# phase_leg_single_2L.net
KiCad netlist of a schematic drawn in Altium Designer
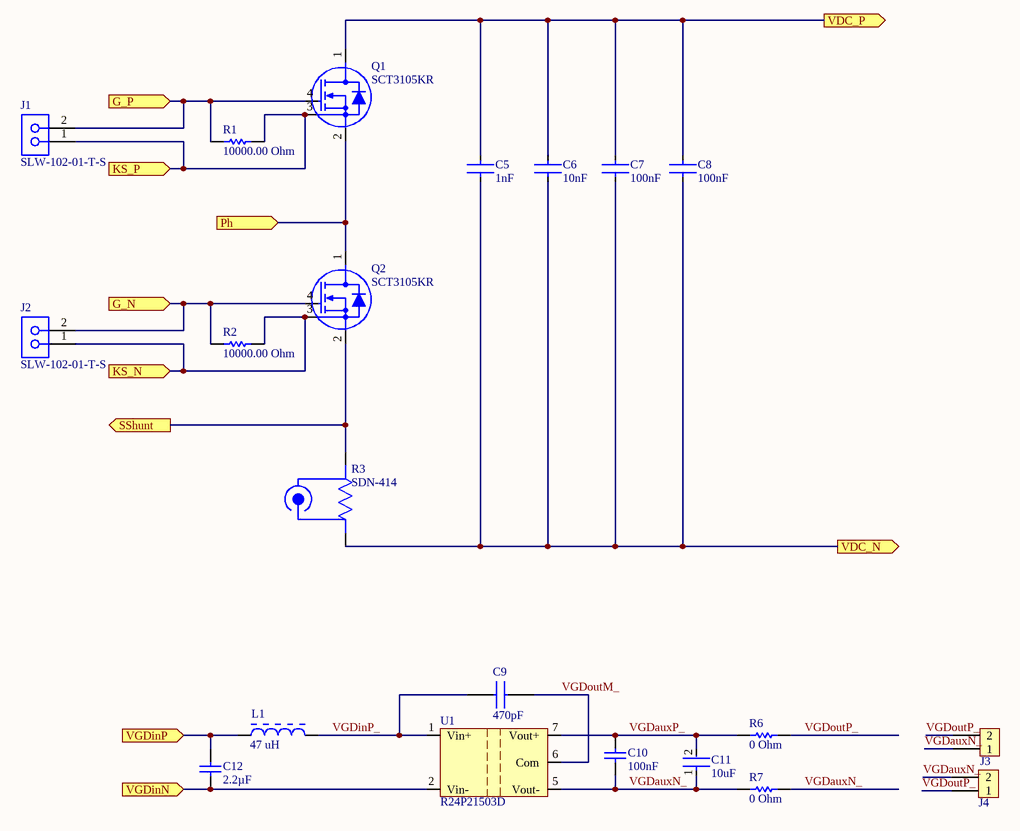
[diagram p0: phase_leg_single_2L.SchDoc]

(export (version "E")
  (design (tool "Eeschema 10.0.6"))
  (components
    (comp (ref "C5")
      (value "C2220C102JGGACTU")
      (footprint "C_2220_L_C2220C102JGGACTU")
      (description "KEMET - C2220C102JGGACTU - KONDENSATOR 1000PF 2 KV 5% C0G/NP0 2220")
      (fields
        (field (name "MANUFACTURER") "KEMET")
        (field (name "CAPACITANCE") "1nF")
        (field (name "TOLERANCE") "5%")
      )
      (libsource (lib "Altium_Library_POWERLAB") (part "C2220C102JGGACTU"))
    )
    (comp (ref "C6")
      (value "C2220C103KDRACTU")
      (footprint "C_2220_L_C2220C103KDRACTU")
      (description "Cap Ceramic 0.01uF 1000V X7R 10% SMD 2220 125C Plastic T/R")
      (fields
        (field (name "MANUFACTURER") "KEMET")
        (field (name "CAPACITANCE") "10nF")
        (field (name "TOLERANCE") "10%")
      )
      (libsource (lib "Altium_Library_POWERLAB") (part "C2220C103KDRACTU"))
    )
    (comp (ref "C7")
      (value "C2220C104KDRACTU")
      (footprint "C_2220_L_C2220C104KDRACTU")
      (description "CAP CER 0.1UF 1KV X7R 2220")
      (fields
        (field (name "MANUFACTURER") "KEMET")
        (field (name "CAPACITANCE") "100nF")
        (field (name "TOLERANCE") "10%")
      )
      (libsource (lib "Altium_Library_POWERLAB") (part "C2220C104KDRACTU"))
    )
    (comp (ref "C8")
      (value "C2220C104KDRACTU")
      (footprint "C_2220_L_C2220C104KDRACTU")
      (description "CAP CER 0.1UF 1KV X7R 2220")
      (fields
        (field (name "MANUFACTURER") "KEMET")
        (field (name "CAPACITANCE") "100nF")
        (field (name "TOLERANCE") "10%")
      )
      (libsource (lib "Altium_Library_POWERLAB") (part "C2220C104KDRACTU"))
    )
    (comp (ref "C9")
      (value "885352211001")
      (footprint "885352211001")
      (description "CAP CER 470PF 250VAC X7R 1812")
      (fields
        (field (name "MANUFACTURER") "Wurth Electronics")
        (field (name "TOLERANCE") "10%")
        (field (name "CAPACITANCE") "470pF")
      )
      (libsource (lib "Altium_Library_POWERLAB") (part "885352211001"))
    )
    (comp (ref "C10")
      (value "100nF")
      (footprint "CAPC0603(1608)100_L")
      (description "CAP 100nF 50V ±5% 0603 (1608 Metric) Thickness 1mm SMD")
      (fields (field (name "TOLERANCE") "Â±5%") (field (name "Comment") "CAP 100nF 50V 0603(1608)"))
      (libsource (lib "Altium Content Vault") (part "CAP"))
    )
    (comp (ref "C11")
      (value "10uF")
      (footprint "FP-GRT31-0_2-MFG")
      (description "CAP CER 10UF 50V X5R 1206")
      (fields
        (field (name "TOLERANCE") "10%")
        (field (name "OCTOPART") "https://octopart.com/grt31cr61h106ke01l-murata-62921736")
      )
      (libsource (lib "Altium Content Vault") (part "11868f565c42a9108669ba33697ecf6"))
    )
    (comp (ref "C12")
      (value "C2012X7R1H225K125AC")
      (footprint "CAPC2013X145X20LL20")
      (description "Chip Capacitor, 2.2 uF, +/- 10%, 50 V, -55 to 125 degC, 0805 (2012 Metric), RoHS, Tape and Reel")
      (fields
        (field (name "MANUFACTURER") "TDK")
        (field (name "TOLERANCE") "±10%")
        (field (name "CAPACITANCE") "2.2µF")
      )
      (libsource (lib "Altium Content Vault") (part "CAP-NP-2"))
    )
    (comp (ref "J1")
      (value "SLW-102-01-T-S")
      (footprint "SMTC-SLW-102-01-X-S")
      (fields (field (name "MANUFACTURER") "Samtec"))
      (libsource (lib "Altium Content Vault") (part "SMTC-SLW-102-01-X-S"))
    )
    (comp (ref "J2")
      (value "SLW-102-01-T-S")
      (footprint "SMTC-SLW-102-01-X-S")
      (fields (field (name "MANUFACTURER") "Samtec"))
      (libsource (lib "Altium Content Vault") (part "SMTC-SLW-102-01-X-S"))
    )
    (comp (ref "J3")
      (value "SSM-102-L-SV")
      (footprint "SSM-102-L-SV")
      (description "SAMTEC - SSM-102-L-SV - RECEPTACLE, 2.54MM, VERT, 2WAY")
      (fields (field (name "MANUFACTURER") "Samtec"))
      (libsource (lib "Altium_Library_POWERLAB") (part "SSM-102-L-SV"))
    )
    (comp (ref "J4")
      (value "SSM-102-L-SV")
      (footprint "SSM-102-L-SV")
      (description "SAMTEC - SSM-102-L-SV - RECEPTACLE, 2.54MM, VERT, 2WAY")
      (fields (field (name "MANUFACTURER") "Samtec"))
      (libsource (lib "Altium_Library_POWERLAB") (part "SSM-102-L-SV"))
    )
    (comp (ref "L1")
      (value "SRN3015-470M")
      (footprint "BOUR-SRN3015-2_V")
      (fields (field (name "INDUCTANCE") "47 uH") (field (name "MANUFACTURER") "Bourns"))
      (libsource (lib "Altium Content Vault") (part "BOUR-IND-2A"))
    )
    (comp (ref "Q1")
      (value "SCT3105KR")
      (footprint "TO-247-4L_hsa")
      (description "N-channel SiC power MOSFET ROHM. Vdss 1200V, Rdson 105mOhm, Id 24A")
      (libsource (lib "Altium_Library_POWERLAB") (part "SCT3105KR"))
    )
    (comp (ref "Q2")
      (value "SCT3105KR")
      (footprint "TO-247-4L_hsa")
      (description "N-channel SiC power MOSFET ROHM. Vdss 1200V, Rdson 105mOhm, Id 24A")
      (libsource (lib "Altium_Library_POWERLAB") (part "SCT3105KR"))
    )
    (comp (ref "R1")
      (value "10000.00 Ohm")
      (footprint "RESC0805(2012)_L")
      (description "10K 0.125W 5% 0805 (2012 Metric)  SMD")
      (fields (field (name "POWER") "0.125 W") (field (name "TOLERANCE") "5 %"))
      (libsource (lib "Altium Content Vault") (part "RES"))
    )
    (comp (ref "R2")
      (value "10000.00 Ohm")
      (footprint "RESC0805(2012)_L")
      (description "10K 0.125W 5% 0805 (2012 Metric)  SMD")
      (fields (field (name "POWER") "0.125 W") (field (name "TOLERANCE") "5 %"))
      (libsource (lib "Altium Content Vault") (part "RES"))
    )
    (comp (ref "R3")
      (value "SDN-414")
      (footprint "SDN-414")
      (description "Coaxial current shunt SDN-414 T&M (New)")
      (fields (field (name "MANUFACTURER") "Ohmite") (field (name "MANUFACTURER PART NUMBER") "WHE10RFET"))
      (libsource (lib "Altium_Library_POWERLAB") (part "SDN-414"))
    )
    (comp (ref "R6")
      (value "0 Ohm")
      (footprint "RESC2013X50X30LL20T20")
      (fields (field (name "MANUFACTURER") "Vishay Dale") (field (name "PART NUMBER") "CRCW08050000Z0EA"))
      (libsource (lib "Altium Content Vault") (part "RES"))
    )
    (comp (ref "R7")
      (value "0 Ohm")
      (footprint "RESC2013X50X30LL20T20")
      (fields (field (name "MANUFACTURER") "Vishay Dale") (field (name "PART NUMBER") "CRCW08050000Z0EA"))
      (libsource (lib "Altium Content Vault") (part "RES"))
    )
    (comp (ref "U1")
      (value "R24P21503D")
      (footprint "SIP-7_R05P22005D")
      (description "2W DC/DC-Converter 'ECONOLINE' SIP7 6.4kV unreg; V. In: 24; V. Out: +15/-03; mA. Out: +93/-185")
      (fields (field (name "MANUFACTURER") "Recom"))
      (libsource (lib "Altium_Library_POWERLAB") (part "R24P21503D"))
    )
  )
  (nets
    (net (code "1") (name "/G_N") (class "Default")
      (node (ref "J2") (pin "2") (pinfunction "2_2") (pintype "passive"))
      (node (ref "Q2") (pin "4") (pinfunction "G_4") (pintype "passive"))
      (node (ref "R2") (pin "2") (pinfunction "2_2") (pintype "passive"))
    )
    (net (code "2") (name "/G_P") (class "Default")
      (node (ref "J1") (pin "2") (pinfunction "2_2") (pintype "passive"))
      (node (ref "Q1") (pin "4") (pinfunction "G_4") (pintype "passive"))
      (node (ref "R1") (pin "1") (pinfunction "1_1") (pintype "passive"))
    )
    (net (code "3") (name "/KS_N") (class "Default")
      (node (ref "J2") (pin "1") (pinfunction "1_1") (pintype "passive"))
      (node (ref "Q2") (pin "3") (pinfunction "KS_3") (pintype "passive"))
      (node (ref "R2") (pin "1") (pinfunction "1_1") (pintype "passive"))
    )
    (net (code "4") (name "/KS_P") (class "Default")
      (node (ref "J1") (pin "1") (pinfunction "1_1") (pintype "passive"))
      (node (ref "Q1") (pin "3") (pinfunction "KS_3") (pintype "passive"))
      (node (ref "R1") (pin "2") (pinfunction "2_2") (pintype "passive"))
    )
    (net (code "5") (name "/Ph") (class "Default")
      (node (ref "Q1") (pin "2") (pinfunction "S_2") (pintype "passive"))
      (node (ref "Q2") (pin "1") (pinfunction "D_1") (pintype "passive"))
    )
    (net (code "6") (name "/SShunt") (class "Default")
      (node (ref "Q2") (pin "2") (pinfunction "S_2") (pintype "passive"))
      (node (ref "R3") (pin "1") (pinfunction "-_1") (pintype "passive"))
    )
    (net (code "7") (name "/VDC_N") (class "Default")
      (node (ref "C5") (pin "1") (pinfunction "1_1") (pintype "passive"))
      (node (ref "C6") (pin "1") (pinfunction "1_1") (pintype "passive"))
      (node (ref "C7") (pin "1") (pinfunction "1_1") (pintype "passive"))
      (node (ref "C8") (pin "1") (pinfunction "1_1") (pintype "passive"))
      (node (ref "R3") (pin "2") (pinfunction "+_2") (pintype "passive"))
    )
    (net (code "8") (name "/VDC_P") (class "Default")
      (node (ref "C5") (pin "2") (pinfunction "2_2") (pintype "passive"))
      (node (ref "C6") (pin "2") (pinfunction "2_2") (pintype "passive"))
      (node (ref "C7") (pin "2") (pinfunction "2_2") (pintype "passive"))
      (node (ref "C8") (pin "2") (pinfunction "2_2") (pintype "passive"))
      (node (ref "Q1") (pin "1") (pinfunction "D_1") (pintype "passive"))
    )
    (net (code "9") (name "/VGDauxN_") (class "Default")
      (node (ref "C10") (pin "1") (pinfunction "1_1") (pintype "passive"))
      (node (ref "C11") (pin "1") (pinfunction "1_1") (pintype "passive"))
      (node (ref "J3") (pin "1") (pinfunction "1_1") (pintype "passive"))
      (node (ref "J4") (pin "2") (pinfunction "2_2") (pintype "passive"))
      (node (ref "R7") (pin "1") (pinfunction "1_1") (pintype "passive"))
      (node (ref "R7") (pin "2") (pinfunction "2_2") (pintype "passive"))
      (node (ref "U1") (pin "5") (pinfunction "Vout-_5") (pintype "passive"))
    )
    (net (code "10") (name "/VGDauxP_") (class "Default")
      (node (ref "C10") (pin "2") (pinfunction "2_2") (pintype "passive"))
      (node (ref "C11") (pin "2") (pinfunction "2_2") (pintype "passive"))
      (node (ref "R6") (pin "2") (pinfunction "2_2") (pintype "passive"))
      (node (ref "U1") (pin "7") (pinfunction "Vout+_7") (pintype "passive"))
    )
    (net (code "11") (name "/VGDinN") (class "Default")
      (node (ref "C12") (pin "2") (pinfunction "2_2") (pintype "passive"))
      (node (ref "U1") (pin "2") (pinfunction "Vin-_2") (pintype "passive"))
    )
    (net (code "12") (name "/VGDinP") (class "Default")
      (node (ref "C12") (pin "1") (pinfunction "1_1") (pintype "passive"))
      (node (ref "L1") (pin "1") (pinfunction "1_1") (pintype "passive"))
    )
    (net (code "13") (name "/VGDinP_") (class "Default")
      (node (ref "C9") (pin "2") (pinfunction "2_2") (pintype "passive"))
      (node (ref "L1") (pin "2") (pinfunction "2_2") (pintype "passive"))
      (node (ref "U1") (pin "1") (pinfunction "Vin+_1") (pintype "passive"))
    )
    (net (code "14") (name "/VGDoutM_") (class "Default")
      (node (ref "C9") (pin "1") (pinfunction "1_1") (pintype "passive"))
      (node (ref "U1") (pin "6") (pinfunction "Com_6") (pintype "passive"))
    )
    (net (code "15") (name "/VGDoutP_") (class "Default")
      (node (ref "J3") (pin "2") (pinfunction "2_2") (pintype "passive"))
      (node (ref "J4") (pin "1") (pinfunction "1_1") (pintype "passive"))
      (node (ref "R6") (pin "1") (pinfunction "1_1") (pintype "passive"))
    )
  )
)
